# TopLevel.net
KiCad netlist of a schematic drawn in Altium Designer
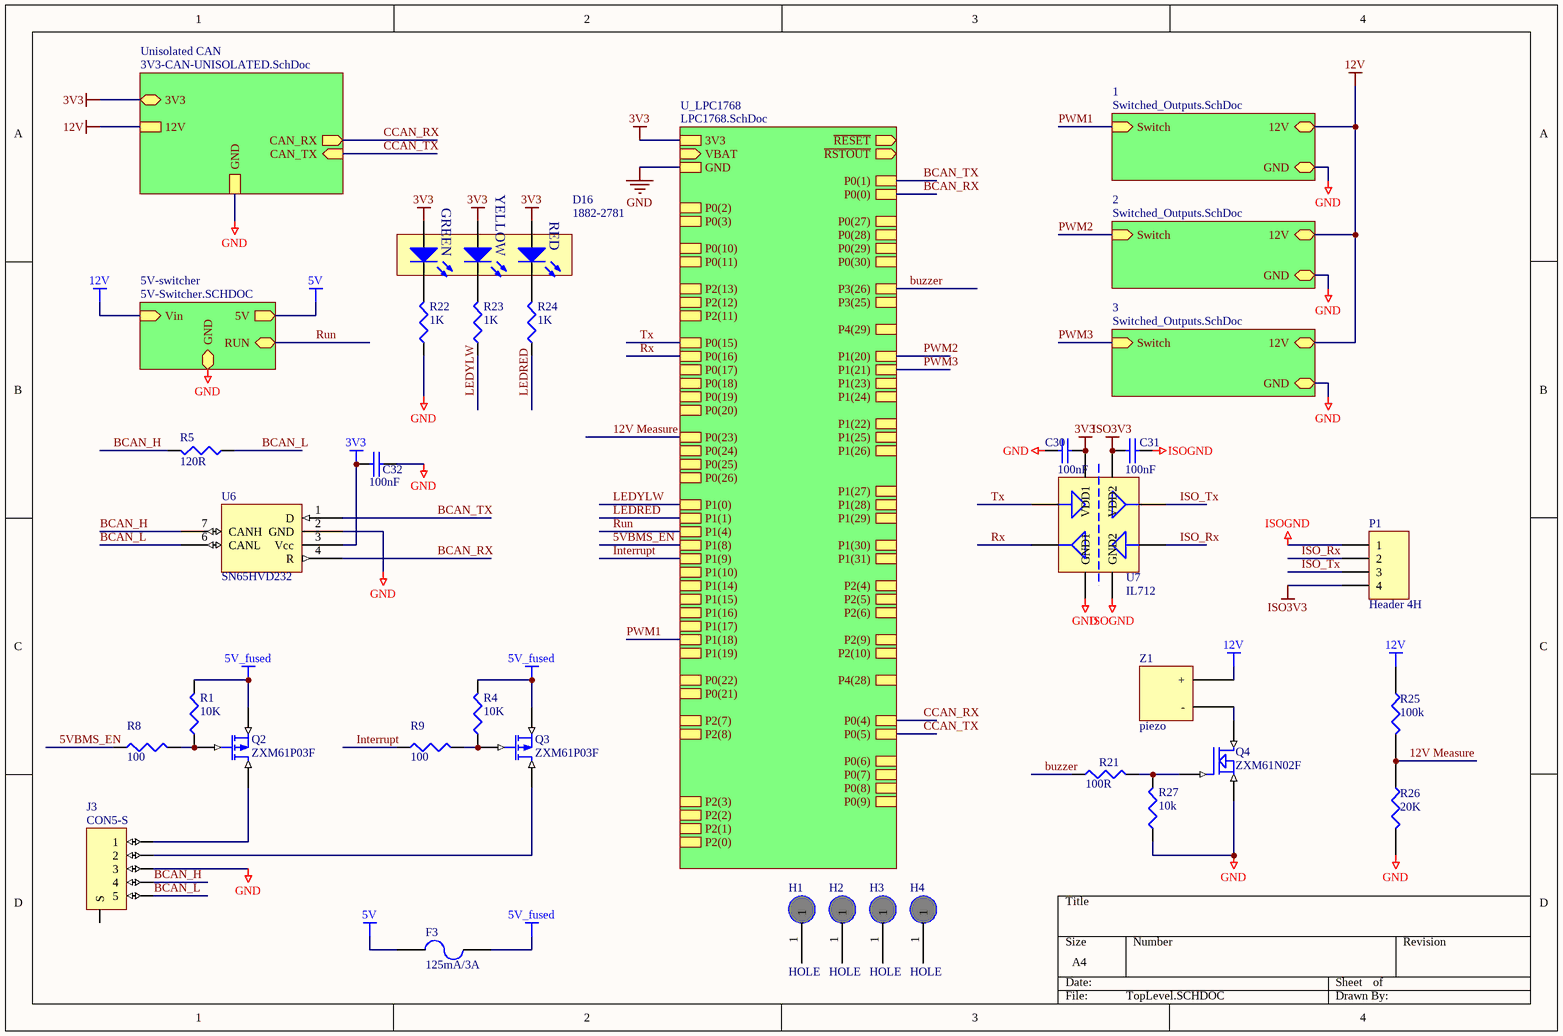
[diagram p0: TopLevel.SCHDOC]

(export (version "E")
  (design (tool "Eeschema 10.0.6"))
  (components
    (comp (ref "C30")
      (value "100nF")
      (footprint "0603")
      (description "Capacitor")
      (libsource (lib "*") (part "CAP"))
    )
    (comp (ref "C31")
      (value "100nF")
      (footprint "0603")
      (description "Capacitor")
      (libsource (lib "*") (part "CAP"))
    )
    (comp (ref "C32")
      (value "100nF")
      (footprint "0603")
      (description "Capacitor")
      (libsource (lib "*") (part "CAP"))
    )
    (comp (ref "D16")
      (value "1882-2781")
      (footprint "LED_TRILEVEL")
      (description "Three level LED")
      (libsource (lib "RCLDQ") (part "LED-TRILEVEL"))
    )
    (comp (ref "F3")
      (value "125mA/3A")
      (footprint "LITTELFUSE-154")
      (description "Fuse")
      (libsource (lib "*") (part "FUSE2"))
    )
    (comp (ref "H1")
      (value "HOLE")
      (footprint "M2.5")
      (description "Hole")
      (libsource (lib "Miscellaneous") (part "HOLE"))
    )
    (comp (ref "H2")
      (value "HOLE")
      (footprint "M2.5")
      (description "Hole")
      (libsource (lib "Miscellaneous") (part "HOLE"))
    )
    (comp (ref "H3")
      (value "HOLE")
      (footprint "M2.5")
      (description "Hole")
      (libsource (lib "Miscellaneous") (part "HOLE"))
    )
    (comp (ref "H4")
      (value "HOLE")
      (footprint "M2.5")
      (description "Hole")
      (libsource (lib "Miscellaneous") (part "HOLE"))
    )
    (comp (ref "J3")
      (value "CON5-S")
      (footprint "TRIAD5F")
      (description "Connector, 2 pin, with shield @ S")
      (libsource (lib "*") (part "CON5-S"))
    )
    (comp (ref "P1")
      (value "Header 4H")
      (footprint "HDR1X4H")
      (description "Header, 4-Pin, Right Angle")
      (fields (field (name "PUBLISHER") "Altium Limited"))
      (libsource (lib "Miscellaneous Connectors") (part "Header 4H"))
    )
    (comp (ref "Q2")
      (value "ZXM61P03F")
      (footprint "SOT23-3")
      (description "1.1A, 30V P-Channel Enhancement mode FET")
      (libsource (lib "RCLDQ") (part "ZXM61P03F"))
    )
    (comp (ref "Q3")
      (value "ZXM61P03F")
      (footprint "SOT23-3")
      (description "1.1A, 30V P-Channel Enhancement mode FET")
      (libsource (lib "RCLDQ") (part "ZXM61P03F"))
    )
    (comp (ref "Q4")
      (value "ZXM61N02F")
      (footprint "SOT23-3")
      (description "1.7A, 20V N-Channel Enhancement mode FET")
      (libsource (lib "RCLDQ") (part "ZXM61N02F"))
    )
    (comp (ref "R1")
      (value "10K")
      (footprint "0603")
      (description "Resistor")
      (libsource (lib "RCLDQ") (part "RES1"))
    )
    (comp (ref "R4")
      (value "10K")
      (footprint "0603")
      (description "Resistor")
      (libsource (lib "RCLDQ") (part "RES1"))
    )
    (comp (ref "R5")
      (value "120R")
      (footprint "0603")
      (description "Resistor")
      (libsource (lib "RCLDQ") (part "RES1"))
    )
    (comp (ref "R8")
      (value "100")
      (footprint "0603")
      (description "Resistor")
      (libsource (lib "RCLDQ") (part "RES1"))
    )
    (comp (ref "R9")
      (value "100")
      (footprint "0603")
      (description "Resistor")
      (libsource (lib "RCLDQ") (part "RES1"))
    )
    (comp (ref "R21") (value "100R") (footprint "0603") (libsource (lib "") (part "RES1_1")))
    (comp (ref "R22")
      (value "1K")
      (footprint "0603")
      (description "Resistor")
      (libsource (lib "RCLDQ") (part "RES1"))
    )
    (comp (ref "R23")
      (value "1K")
      (footprint "0603")
      (description "Resistor")
      (libsource (lib "RCLDQ") (part "RES1"))
    )
    (comp (ref "R24")
      (value "1K")
      (footprint "0603")
      (description "Resistor")
      (libsource (lib "RCLDQ") (part "RES1"))
    )
    (comp (ref "R25") (value "100k") (footprint "1206") (libsource (lib "*") (part "RES1")))
    (comp (ref "R26") (value "20K") (footprint "1206") (libsource (lib "*") (part "RES1")))
    (comp (ref "R27") (value "10k") (footprint "0603") (libsource (lib "") (part "RES1_1")))
    (comp (ref "U6")
      (value "SN65HVD232")
      (footprint "SO8")
      (description "3.3V CAN Transciever")
      (libsource (lib "*") (part "SN65HVD232"))
    )
    (comp (ref "U7")
      (value "IL712")
      (footprint "SO8")
      (description "IL712 Optical Isolator")
      (libsource (lib "Optocouplers") (part "IL712"))
    )
    (comp (ref "Z1") (value "piezo") (footprint "piezo") (libsource (lib "BMS") (part "piezo")))
  )
  (nets
    (net (code "1") (name "/5VBMS_EN") (class "Default")
      (node (ref "R8") (pin "1") (pinfunction "1_1") (pintype "passive"))
    )
    (net (code "2") (name "/12V Measure") (class "Default")
      (node (ref "R25") (pin "2") (pinfunction "2_2") (pintype "passive"))
      (node (ref "R26") (pin "1") (pinfunction "1_1") (pintype "passive"))
    )
    (net (code "3") (name "/BCAN_H") (class "Default")
      (node (ref "J3") (pin "4") (pinfunction "4_4") (pintype "bidirectional"))
      (node (ref "R5") (pin "2") (pinfunction "2_2") (pintype "passive"))
      (node (ref "U6") (pin "7") (pinfunction "CANH_7") (pintype "bidirectional"))
    )
    (net (code "4") (name "/BCAN_L") (class "Default")
      (node (ref "J3") (pin "5") (pinfunction "5_5") (pintype "bidirectional"))
      (node (ref "R5") (pin "1") (pinfunction "1_1") (pintype "passive"))
      (node (ref "U6") (pin "6") (pinfunction "CANL_6") (pintype "bidirectional"))
    )
    (net (code "5") (name "/BCAN_RX") (class "Default")
      (node (ref "U6") (pin "4") (pinfunction "R_4") (pintype "output"))
    )
    (net (code "6") (name "/BCAN_TX") (class "Default")
      (node (ref "U6") (pin "1") (pinfunction "D_1") (pintype "input"))
    )
    (net (code "9") (name "/ISO_Rx") (class "Default")
      (node (ref "P1") (pin "2") (pinfunction "2_2") (pintype "passive"))
      (node (ref "U7") (pin "6") (pinfunction "IN2_6") (pintype "passive"))
    )
    (net (code "10") (name "/ISO_Tx") (class "Default")
      (node (ref "P1") (pin "3") (pinfunction "3_3") (pintype "passive"))
      (node (ref "U7") (pin "7") (pinfunction "OUT1_7") (pintype "passive"))
    )
    (net (code "11") (name "/Interrupt") (class "Default")
      (node (ref "R9") (pin "1") (pinfunction "1_1") (pintype "passive"))
    )
    (net (code "12") (name "/LEDRED") (class "Default")
      (node (ref "R24") (pin "1") (pinfunction "1_1") (pintype "passive"))
    )
    (net (code "13") (name "/LEDYLW") (class "Default")
      (node (ref "R23") (pin "1") (pinfunction "1_1") (pintype "passive"))
    )
    (net (code "72") (name "/Rx") (class "Default")
      (node (ref "U7") (pin "3") (pinfunction "OUT2_3") (pintype "passive"))
    )
    (net (code "73") (name "/Tx") (class "Default")
      (node (ref "U7") (pin "2") (pinfunction "IN1_2") (pintype "passive"))
    )
    (net (code "75") (name "/buzzer") (class "Default")
      (node (ref "R21") (pin "1") (pinfunction "1_1") (pintype "passive"))
    )
    (net (code "78") (name "3V3") (class "Default")
      (node (ref "C30") (pin "2") (pinfunction "2_2") (pintype "passive"))
      (node (ref "C32") (pin "2") (pinfunction "2_2") (pintype "passive"))
      (node (ref "D16") (pin "4") (pinfunction "A_4") (pintype "passive"))
      (node (ref "D16") (pin "5") (pinfunction "A_5") (pintype "passive"))
      (node (ref "D16") (pin "6") (pinfunction "A_6") (pintype "passive"))
      (node (ref "U6") (pin "3") (pinfunction "Vcc_3") (pintype "power_in"))
      (node (ref "U7") (pin "1") (pinfunction "VDD1_1") (pintype "passive"))
    )
    (net (code "79") (name "5V") (class "Default")
      (node (ref "F3") (pin "2") (pinfunction "2_2") (pintype "passive"))
    )
    (net (code "80") (name "5V_fused") (class "Default")
      (node (ref "F3") (pin "1") (pinfunction "1_1") (pintype "passive"))
      (node (ref "Q2") (pin "2") (pinfunction "D_2") (pintype "input"))
      (node (ref "Q3") (pin "2") (pinfunction "D_2") (pintype "input"))
      (node (ref "R1") (pin "2") (pinfunction "2_2") (pintype "passive"))
      (node (ref "R4") (pin "2") (pinfunction "2_2") (pintype "passive"))
    )
    (net (code "81") (name "12V") (class "Default")
      (node (ref "R25") (pin "1") (pinfunction "1_1") (pintype "passive"))
      (node (ref "Z1") (pin "1") (pinfunction "+_1") (pintype "passive"))
    )
    (net (code "82") (name "GND") (class "Default")
      (node (ref "C30") (pin "1") (pinfunction "1_1") (pintype "passive"))
      (node (ref "C32") (pin "1") (pinfunction "1_1") (pintype "passive"))
      (node (ref "J3") (pin "3") (pinfunction "3_3") (pintype "bidirectional"))
      (node (ref "Q4") (pin "2") (pinfunction "S_2") (pintype "input"))
      (node (ref "R22") (pin "1") (pinfunction "1_1") (pintype "passive"))
      (node (ref "R26") (pin "2") (pinfunction "2_2") (pintype "passive"))
      (node (ref "R27") (pin "1") (pinfunction "1_1") (pintype "passive"))
      (node (ref "U6") (pin "2") (pinfunction "GND_2") (pintype "power_in"))
      (node (ref "U7") (pin "4") (pinfunction "GND1_4") (pintype "passive"))
    )
    (net (code "83") (name "ISO3V3") (class "Default")
      (node (ref "C31") (pin "1") (pinfunction "1_1") (pintype "passive"))
      (node (ref "P1") (pin "4") (pinfunction "4_4") (pintype "passive"))
      (node (ref "U7") (pin "8") (pinfunction "VDD2_8") (pintype "passive"))
    )
    (net (code "84") (name "ISOGND") (class "Default")
      (node (ref "C31") (pin "2") (pinfunction "2_2") (pintype "passive"))
      (node (ref "P1") (pin "1") (pinfunction "1_1") (pintype "passive"))
      (node (ref "U7") (pin "5") (pinfunction "GND2_5") (pintype "passive"))
    )
    (net (code "85") (name "Net-(D16-K-Pad1)") (class "Default")
      (node (ref "D16") (pin "1") (pinfunction "K_1") (pintype "passive"))
      (node (ref "R22") (pin "2") (pinfunction "2_2") (pintype "passive"))
    )
    (net (code "86") (name "Net-(D16-K-Pad2)") (class "Default")
      (node (ref "D16") (pin "2") (pinfunction "K_2") (pintype "passive"))
      (node (ref "R23") (pin "2") (pinfunction "2_2") (pintype "passive"))
    )
    (net (code "87") (name "Net-(D16-K-Pad3)") (class "Default")
      (node (ref "D16") (pin "3") (pinfunction "K_3") (pintype "passive"))
      (node (ref "R24") (pin "2") (pinfunction "2_2") (pintype "passive"))
    )
    (net (code "88") (name "Net-(Q2-G)") (class "Default")
      (node (ref "Q2") (pin "1") (pinfunction "G_1") (pintype "input"))
      (node (ref "R1") (pin "1") (pinfunction "1_1") (pintype "passive"))
      (node (ref "R8") (pin "2") (pinfunction "2_2") (pintype "passive"))
    )
    (net (code "89") (name "Net-(Q2-S)") (class "Default")
      (node (ref "J3") (pin "1") (pinfunction "1_1") (pintype "bidirectional"))
      (node (ref "Q2") (pin "3") (pinfunction "S_3") (pintype "input"))
    )
    (net (code "90") (name "Net-(Q3-G)") (class "Default")
      (node (ref "Q3") (pin "1") (pinfunction "G_1") (pintype "input"))
      (node (ref "R4") (pin "1") (pinfunction "1_1") (pintype "passive"))
      (node (ref "R9") (pin "2") (pinfunction "2_2") (pintype "passive"))
    )
    (net (code "91") (name "Net-(Q3-S)") (class "Default")
      (node (ref "J3") (pin "2") (pinfunction "2_2") (pintype "bidirectional"))
      (node (ref "Q3") (pin "3") (pinfunction "S_3") (pintype "input"))
    )
    (net (code "92") (name "Net-(Q4-D)") (class "Default")
      (node (ref "Q4") (pin "3") (pinfunction "D_3") (pintype "input"))
      (node (ref "Z1") (pin "2") (pinfunction "-_2") (pintype "passive"))
    )
    (net (code "93") (name "Net-(Q4-G)") (class "Default")
      (node (ref "Q4") (pin "1") (pinfunction "G_1") (pintype "input"))
      (node (ref "R21") (pin "2") (pinfunction "2_2") (pintype "passive"))
      (node (ref "R27") (pin "2") (pinfunction "2_2") (pintype "passive"))
    )
    (net (code "94") (name "unconnected-(H1-Pad1)") (class "Default")
      (node (ref "H1") (pin "1") (pinfunction "1_1") (pintype "passive"))
    )
    (net (code "95") (name "unconnected-(H2-Pad1)") (class "Default")
      (node (ref "H2") (pin "1") (pinfunction "1_1") (pintype "passive"))
    )
    (net (code "96") (name "unconnected-(H3-Pad1)") (class "Default")
      (node (ref "H3") (pin "1") (pinfunction "1_1") (pintype "passive"))
    )
    (net (code "97") (name "unconnected-(H4-Pad1)") (class "Default")
      (node (ref "H4") (pin "1") (pinfunction "1_1") (pintype "passive"))
    )
    (net (code "98") (name "unconnected-(J3-S-Pad0)") (class "Default")
      (node (ref "J3") (pin "0") (pinfunction "S_0") (pintype "bidirectional"))
    )
  )
)
